# radar1.net
KiCad netlist of a schematic drawn in EAGLE
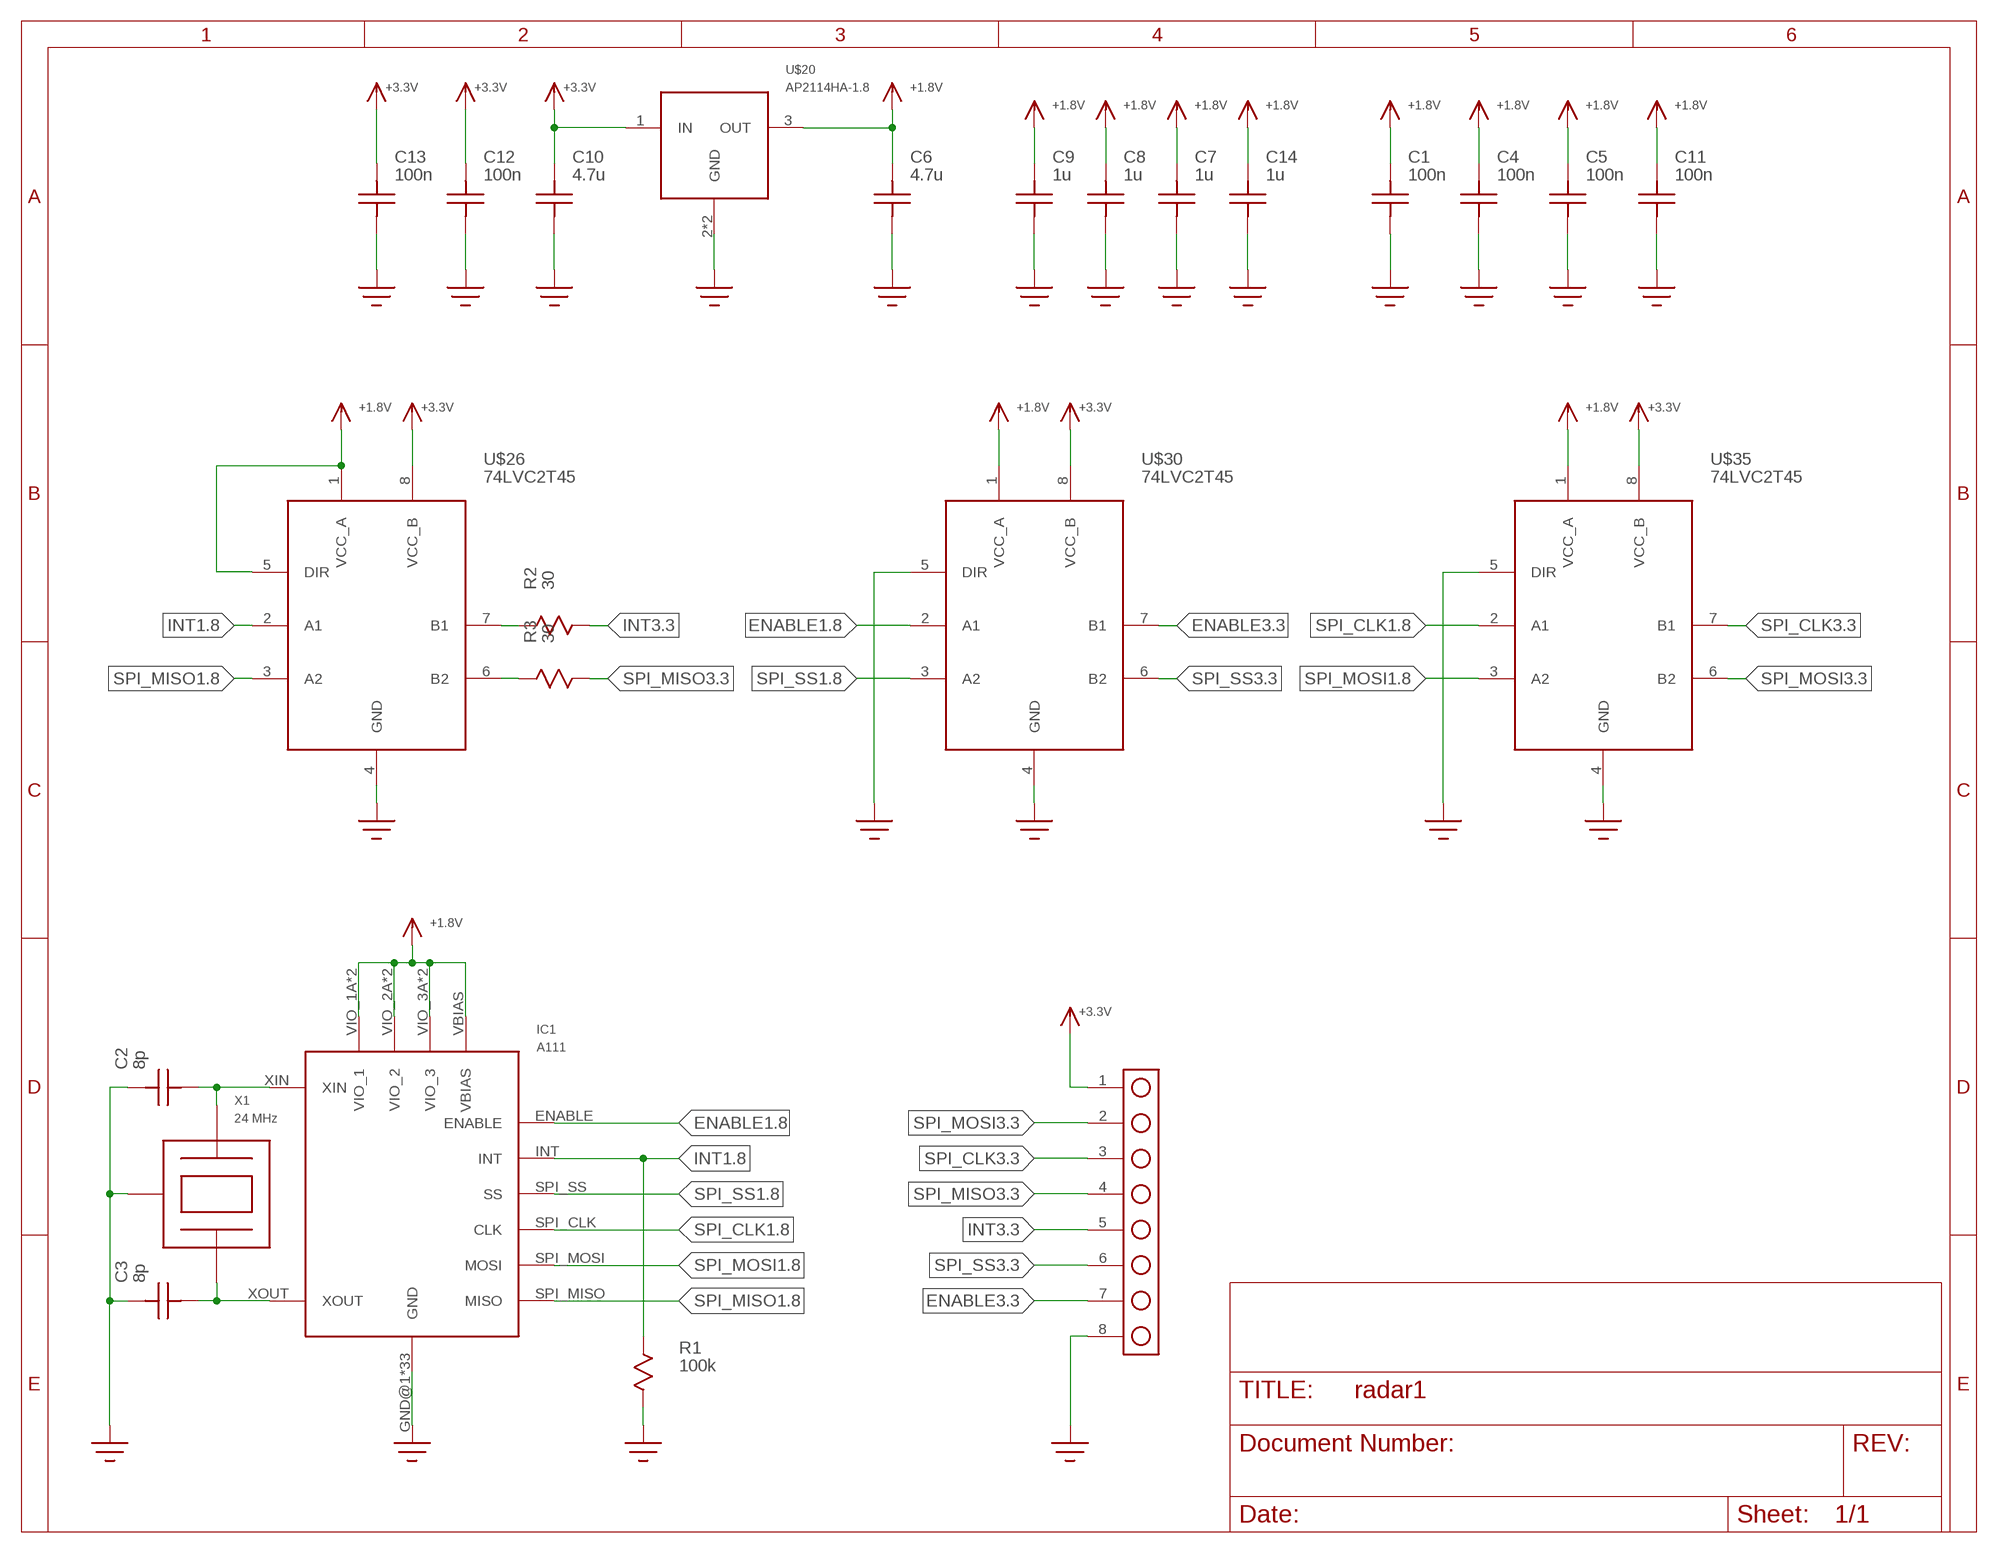
[diagram p0: schematic, sheet 1]

(export (version "E")
  (design (tool "Eeschema 10.0.6"))
  (components
    (comp (ref "C1")
      (value "100n")
      (footprint "eagle-import:C0402")
      (libsource (lib "eagle-import") (part "C"))
    )
    (comp (ref "C2")
      (value "8p")
      (footprint "eagle-import:C0402")
      (libsource (lib "eagle-import") (part "C"))
    )
    (comp (ref "C3")
      (value "8p")
      (footprint "eagle-import:C0402")
      (libsource (lib "eagle-import") (part "C"))
    )
    (comp (ref "C4")
      (value "100n")
      (footprint "eagle-import:C0402")
      (libsource (lib "eagle-import") (part "C"))
    )
    (comp (ref "C5")
      (value "100n")
      (footprint "eagle-import:C0402")
      (libsource (lib "eagle-import") (part "C"))
    )
    (comp (ref "C6")
      (value "4.7u")
      (footprint "eagle-import:C0603")
      (libsource (lib "eagle-import") (part "C0603"))
    )
    (comp (ref "C7")
      (value "1u")
      (footprint "eagle-import:C0603")
      (libsource (lib "eagle-import") (part "C0603"))
    )
    (comp (ref "C8")
      (value "1u")
      (footprint "eagle-import:C0603")
      (libsource (lib "eagle-import") (part "C0603"))
    )
    (comp (ref "C9")
      (value "1u")
      (footprint "eagle-import:C0603")
      (libsource (lib "eagle-import") (part "C0603"))
    )
    (comp (ref "C10")
      (value "4.7u")
      (footprint "eagle-import:1206")
      (libsource (lib "eagle-import") (part "C1206"))
    )
    (comp (ref "C11")
      (value "100n")
      (footprint "eagle-import:C0402")
      (libsource (lib "eagle-import") (part "C"))
    )
    (comp (ref "C12")
      (value "100n")
      (footprint "eagle-import:C0402")
      (libsource (lib "eagle-import") (part "C"))
    )
    (comp (ref "C13")
      (value "100n")
      (footprint "eagle-import:C0402")
      (libsource (lib "eagle-import") (part "C"))
    )
    (comp (ref "C14")
      (value "1u")
      (footprint "eagle-import:C0603")
      (libsource (lib "eagle-import") (part "C0603"))
    )
    (comp (ref "IC1")
      (value "A111")
      (footprint "eagle-import:A111")
      (libsource (lib "eagle-import") (part "A111"))
    )
    (comp (ref "J1")
      (value "HEADER_8_PIN")
      (footprint "eagle-import:HEADER_8_PIN")
      (libsource (lib "eagle-import") (part "HEADER_8_PIN"))
    )
    (comp (ref "R1")
      (value "100k")
      (footprint "eagle-import:R0603")
      (libsource (lib "eagle-import") (part "R0603"))
    )
    (comp (ref "R2")
      (value "30")
      (footprint "eagle-import:R0603")
      (libsource (lib "eagle-import") (part "R0603"))
    )
    (comp (ref "R3")
      (value "30")
      (footprint "eagle-import:R0603")
      (libsource (lib "eagle-import") (part "R0603"))
    )
    (comp (ref "U$20")
      (value "AP2114HA-1.8")
      (footprint "eagle-import:SOT-223")
      (libsource (lib "eagle-import") (part "AP2114"))
    )
    (comp (ref "U$26")
      (value "74LVC2T45")
      (footprint "eagle-import:SM8")
      (libsource (lib "eagle-import") (part "74LVC2T45"))
    )
    (comp (ref "U$30")
      (value "74LVC2T45")
      (footprint "eagle-import:SM8")
      (libsource (lib "eagle-import") (part "74LVC2T45"))
    )
    (comp (ref "U$35")
      (value "74LVC2T45")
      (footprint "eagle-import:SM8")
      (libsource (lib "eagle-import") (part "74LVC2T45"))
    )
    (comp (ref "X1")
      (value "24 MHz")
      (footprint "eagle-import:CRYSTAL_3.2X2.5")
      (libsource (lib "eagle-import") (part "XTAL"))
    )
  )
  (nets
    (net (code "1") (name "+1.8V") (class "Default")
      (node (ref "C1") (pin "2") (pinfunction "P$2_2") (pintype "bidirectional"))
      (node (ref "C11") (pin "2") (pinfunction "P$2_2") (pintype "bidirectional"))
      (node (ref "C14") (pin "P$2") (pinfunction "P$2_P$2") (pintype "bidirectional"))
      (node (ref "C4") (pin "2") (pinfunction "P$2_2") (pintype "bidirectional"))
      (node (ref "C5") (pin "2") (pinfunction "P$2_2") (pintype "bidirectional"))
      (node (ref "C6") (pin "P$2") (pinfunction "P$2_P$2") (pintype "bidirectional"))
      (node (ref "C7") (pin "P$2") (pinfunction "P$2_P$2") (pintype "bidirectional"))
      (node (ref "C8") (pin "P$2") (pinfunction "P$2_P$2") (pintype "bidirectional"))
      (node (ref "C9") (pin "P$2") (pinfunction "P$2_P$2") (pintype "bidirectional"))
      (node (ref "IC1") (pin "VBIAS") (pinfunction "VBIAS_VBIAS") (pintype "bidirectional"))
      (node (ref "IC1") (pin "VIO_1A") (pinfunction "VIO_1_VIO_1A") (pintype "bidirectional"))
      (node (ref "IC1") (pin "VIO_1B") (pinfunction "VIO_1_VIO_1B") (pintype "bidirectional"))
      (node (ref "IC1") (pin "VIO_2A") (pinfunction "VIO_2_VIO_2A") (pintype "bidirectional"))
      (node (ref "IC1") (pin "VIO_2B") (pinfunction "VIO_2_VIO_2B") (pintype "bidirectional"))
      (node (ref "IC1") (pin "VIO_3A") (pinfunction "VIO_3_VIO_3A") (pintype "bidirectional"))
      (node (ref "IC1") (pin "VIO_3B") (pinfunction "VIO_3_VIO_3B") (pintype "bidirectional"))
      (node (ref "U$20") (pin "3") (pinfunction "OUT_3") (pintype "bidirectional"))
      (node (ref "U$26") (pin "1") (pinfunction "VCC_A_1") (pintype "bidirectional"))
      (node (ref "U$26") (pin "5") (pinfunction "DIR_5") (pintype "bidirectional"))
      (node (ref "U$30") (pin "1") (pinfunction "VCC_A_1") (pintype "bidirectional"))
      (node (ref "U$35") (pin "1") (pinfunction "VCC_A_1") (pintype "bidirectional"))
    )
    (net (code "2") (name "+3.3V") (class "Default")
      (node (ref "C10") (pin "P$2") (pinfunction "P$2_P$2") (pintype "bidirectional"))
      (node (ref "C12") (pin "2") (pinfunction "P$2_2") (pintype "bidirectional"))
      (node (ref "C13") (pin "2") (pinfunction "P$2_2") (pintype "bidirectional"))
      (node (ref "J1") (pin "1") (pinfunction "1_1") (pintype "bidirectional"))
      (node (ref "U$20") (pin "1") (pinfunction "IN_1") (pintype "bidirectional"))
      (node (ref "U$26") (pin "8") (pinfunction "VCC_B_8") (pintype "bidirectional"))
      (node (ref "U$30") (pin "8") (pinfunction "VCC_B_8") (pintype "bidirectional"))
      (node (ref "U$35") (pin "8") (pinfunction "VCC_B_8") (pintype "bidirectional"))
    )
    (net (code "3") (name "ENABLE1.8") (class "Default")
      (node (ref "IC1") (pin "ENABLE") (pinfunction "ENABLE_ENABLE") (pintype "bidirectional"))
      (node (ref "U$30") (pin "2") (pinfunction "A1_2") (pintype "bidirectional"))
    )
    (net (code "4") (name "ENABLE3.3") (class "Default")
      (node (ref "J1") (pin "7") (pinfunction "7_7") (pintype "bidirectional"))
      (node (ref "U$30") (pin "7") (pinfunction "B1_7") (pintype "bidirectional"))
    )
    (net (code "5") (name "GND") (class "Default")
      (node (ref "C1") (pin "1") (pinfunction "P$1_1") (pintype "bidirectional"))
      (node (ref "C10") (pin "P$1") (pinfunction "P$1_P$1") (pintype "bidirectional"))
      (node (ref "C11") (pin "1") (pinfunction "P$1_1") (pintype "bidirectional"))
      (node (ref "C12") (pin "1") (pinfunction "P$1_1") (pintype "bidirectional"))
      (node (ref "C13") (pin "1") (pinfunction "P$1_1") (pintype "bidirectional"))
      (node (ref "C14") (pin "P$1") (pinfunction "P$1_P$1") (pintype "bidirectional"))
      (node (ref "C2") (pin "2") (pinfunction "P$2_2") (pintype "bidirectional"))
      (node (ref "C3") (pin "2") (pinfunction "P$2_2") (pintype "bidirectional"))
      (node (ref "C4") (pin "1") (pinfunction "P$1_1") (pintype "bidirectional"))
      (node (ref "C5") (pin "1") (pinfunction "P$1_1") (pintype "bidirectional"))
      (node (ref "C6") (pin "P$1") (pinfunction "P$1_P$1") (pintype "bidirectional"))
      (node (ref "C7") (pin "P$1") (pinfunction "P$1_P$1") (pintype "bidirectional"))
      (node (ref "C8") (pin "P$1") (pinfunction "P$1_P$1") (pintype "bidirectional"))
      (node (ref "C9") (pin "P$1") (pinfunction "P$1_P$1") (pintype "bidirectional"))
      (node (ref "IC1") (pin "GND@1") (pinfunction "GND_GND@1") (pintype "bidirectional"))
      (node (ref "IC1") (pin "GND@10") (pinfunction "GND_GND@10") (pintype "bidirectional"))
      (node (ref "IC1") (pin "GND@11") (pinfunction "GND_GND@11") (pintype "bidirectional"))
      (node (ref "IC1") (pin "GND@12") (pinfunction "GND_GND@12") (pintype "bidirectional"))
      (node (ref "IC1") (pin "GND@13") (pinfunction "GND_GND@13") (pintype "bidirectional"))
      (node (ref "IC1") (pin "GND@14") (pinfunction "GND_GND@14") (pintype "bidirectional"))
      (node (ref "IC1") (pin "GND@15") (pinfunction "GND_GND@15") (pintype "bidirectional"))
      (node (ref "IC1") (pin "GND@16") (pinfunction "GND_GND@16") (pintype "bidirectional"))
      (node (ref "IC1") (pin "GND@17") (pinfunction "GND_GND@17") (pintype "bidirectional"))
      (node (ref "IC1") (pin "GND@18") (pinfunction "GND_GND@18") (pintype "bidirectional"))
      (node (ref "IC1") (pin "GND@19") (pinfunction "GND_GND@19") (pintype "bidirectional"))
      (node (ref "IC1") (pin "GND@2") (pinfunction "GND_GND@2") (pintype "bidirectional"))
      (node (ref "IC1") (pin "GND@20") (pinfunction "GND_GND@20") (pintype "bidirectional"))
      (node (ref "IC1") (pin "GND@21") (pinfunction "GND_GND@21") (pintype "bidirectional"))
      (node (ref "IC1") (pin "GND@22") (pinfunction "GND_GND@22") (pintype "bidirectional"))
      (node (ref "IC1") (pin "GND@23") (pinfunction "GND_GND@23") (pintype "bidirectional"))
      (node (ref "IC1") (pin "GND@24") (pinfunction "GND_GND@24") (pintype "bidirectional"))
      (node (ref "IC1") (pin "GND@25") (pinfunction "GND_GND@25") (pintype "bidirectional"))
      (node (ref "IC1") (pin "GND@26") (pinfunction "GND_GND@26") (pintype "bidirectional"))
      (node (ref "IC1") (pin "GND@27") (pinfunction "GND_GND@27") (pintype "bidirectional"))
      (node (ref "IC1") (pin "GND@28") (pinfunction "GND_GND@28") (pintype "bidirectional"))
      (node (ref "IC1") (pin "GND@29") (pinfunction "GND_GND@29") (pintype "bidirectional"))
      (node (ref "IC1") (pin "GND@3") (pinfunction "GND_GND@3") (pintype "bidirectional"))
      (node (ref "IC1") (pin "GND@30") (pinfunction "GND_GND@30") (pintype "bidirectional"))
      (node (ref "IC1") (pin "GND@31") (pinfunction "GND_GND@31") (pintype "bidirectional"))
      (node (ref "IC1") (pin "GND@32") (pinfunction "GND_GND@32") (pintype "bidirectional"))
      (node (ref "IC1") (pin "GND@33") (pinfunction "GND_GND@33") (pintype "bidirectional"))
      (node (ref "IC1") (pin "GND@4") (pinfunction "GND_GND@4") (pintype "bidirectional"))
      (node (ref "IC1") (pin "GND@5") (pinfunction "GND_GND@5") (pintype "bidirectional"))
      (node (ref "IC1") (pin "GND@6") (pinfunction "GND_GND@6") (pintype "bidirectional"))
      (node (ref "IC1") (pin "GND@7") (pinfunction "GND_GND@7") (pintype "bidirectional"))
      (node (ref "IC1") (pin "GND@8") (pinfunction "GND_GND@8") (pintype "bidirectional"))
      (node (ref "IC1") (pin "GND@9") (pinfunction "GND_GND@9") (pintype "bidirectional"))
      (node (ref "J1") (pin "8") (pinfunction "8_8") (pintype "bidirectional"))
      (node (ref "R1") (pin "P$2") (pinfunction "P$4_P$2") (pintype "bidirectional"))
      (node (ref "U$20") (pin "2") (pinfunction "GND_2") (pintype "bidirectional"))
      (node (ref "U$20") (pin "4") (pinfunction "GND_4") (pintype "bidirectional"))
      (node (ref "U$26") (pin "4") (pinfunction "GND_4") (pintype "bidirectional"))
      (node (ref "U$30") (pin "4") (pinfunction "GND_4") (pintype "bidirectional"))
      (node (ref "U$30") (pin "5") (pinfunction "DIR_5") (pintype "bidirectional"))
      (node (ref "U$35") (pin "4") (pinfunction "GND_4") (pintype "bidirectional"))
      (node (ref "U$35") (pin "5") (pinfunction "DIR_5") (pintype "bidirectional"))
      (node (ref "X1") (pin "P$2") (pinfunction "P$CASE_P$2") (pintype "bidirectional"))
      (node (ref "X1") (pin "P$4") (pinfunction "P$CASE_P$4") (pintype "bidirectional"))
    )
    (net (code "6") (name "INT1.8") (class "Default")
      (node (ref "IC1") (pin "INT") (pinfunction "INT_INT") (pintype "bidirectional"))
      (node (ref "R1") (pin "P$1") (pinfunction "P$3_P$1") (pintype "bidirectional"))
      (node (ref "U$26") (pin "2") (pinfunction "A1_2") (pintype "bidirectional"))
    )
    (net (code "7") (name "INT3.3") (class "Default")
      (node (ref "J1") (pin "5") (pinfunction "5_5") (pintype "bidirectional"))
      (node (ref "R2") (pin "P$2") (pinfunction "P$4_P$2") (pintype "bidirectional"))
    )
    (net (code "8") (name "Net-(C2-P$1)") (class "Default")
      (node (ref "C2") (pin "1") (pinfunction "P$1_1") (pintype "bidirectional"))
      (node (ref "IC1") (pin "XIN") (pinfunction "XIN_XIN") (pintype "bidirectional"))
      (node (ref "X1") (pin "P$1") (pinfunction "P$X1_P$1") (pintype "bidirectional"))
    )
    (net (code "9") (name "Net-(C3-P$1)") (class "Default")
      (node (ref "C3") (pin "1") (pinfunction "P$1_1") (pintype "bidirectional"))
      (node (ref "IC1") (pin "XOUT") (pinfunction "XOUT_XOUT") (pintype "bidirectional"))
      (node (ref "X1") (pin "P$3") (pinfunction "P$X2_P$3") (pintype "bidirectional"))
    )
    (net (code "10") (name "Net-(R2-P$3)") (class "Default")
      (node (ref "R2") (pin "P$1") (pinfunction "P$3_P$1") (pintype "bidirectional"))
      (node (ref "U$26") (pin "7") (pinfunction "B1_7") (pintype "bidirectional"))
    )
    (net (code "11") (name "Net-(R3-P$3)") (class "Default")
      (node (ref "R3") (pin "P$1") (pinfunction "P$3_P$1") (pintype "bidirectional"))
      (node (ref "U$26") (pin "6") (pinfunction "B2_6") (pintype "bidirectional"))
    )
    (net (code "12") (name "SPI_CLK1.8") (class "Default")
      (node (ref "IC1") (pin "SPI_CLK") (pinfunction "CLK_SPI_CLK") (pintype "bidirectional"))
      (node (ref "U$35") (pin "2") (pinfunction "A1_2") (pintype "bidirectional"))
    )
    (net (code "13") (name "SPI_CLK3.3") (class "Default")
      (node (ref "J1") (pin "3") (pinfunction "3_3") (pintype "bidirectional"))
      (node (ref "U$35") (pin "7") (pinfunction "B1_7") (pintype "bidirectional"))
    )
    (net (code "14") (name "SPI_MISO1.8") (class "Default")
      (node (ref "IC1") (pin "SPI_MISO") (pinfunction "MISO_SPI_MISO") (pintype "bidirectional"))
      (node (ref "U$26") (pin "3") (pinfunction "A2_3") (pintype "bidirectional"))
    )
    (net (code "15") (name "SPI_MISO3.3") (class "Default")
      (node (ref "J1") (pin "4") (pinfunction "4_4") (pintype "bidirectional"))
      (node (ref "R3") (pin "P$2") (pinfunction "P$4_P$2") (pintype "bidirectional"))
    )
    (net (code "16") (name "SPI_MOSI1.8") (class "Default")
      (node (ref "IC1") (pin "SPI_MOSI") (pinfunction "MOSI_SPI_MOSI") (pintype "bidirectional"))
      (node (ref "U$35") (pin "3") (pinfunction "A2_3") (pintype "bidirectional"))
    )
    (net (code "17") (name "SPI_MOSI3.3") (class "Default")
      (node (ref "J1") (pin "2") (pinfunction "2_2") (pintype "bidirectional"))
      (node (ref "U$35") (pin "6") (pinfunction "B2_6") (pintype "bidirectional"))
    )
    (net (code "18") (name "SPI_SS1.8") (class "Default")
      (node (ref "IC1") (pin "SPI_SS") (pinfunction "SS_SPI_SS") (pintype "bidirectional"))
      (node (ref "U$30") (pin "3") (pinfunction "A2_3") (pintype "bidirectional"))
    )
    (net (code "19") (name "SPI_SS3.3") (class "Default")
      (node (ref "J1") (pin "6") (pinfunction "6_6") (pintype "bidirectional"))
      (node (ref "U$30") (pin "6") (pinfunction "B2_6") (pintype "bidirectional"))
    )
  )
)
